# CAN_Module.net
KiCad netlist of a schematic drawn in Altium Designer
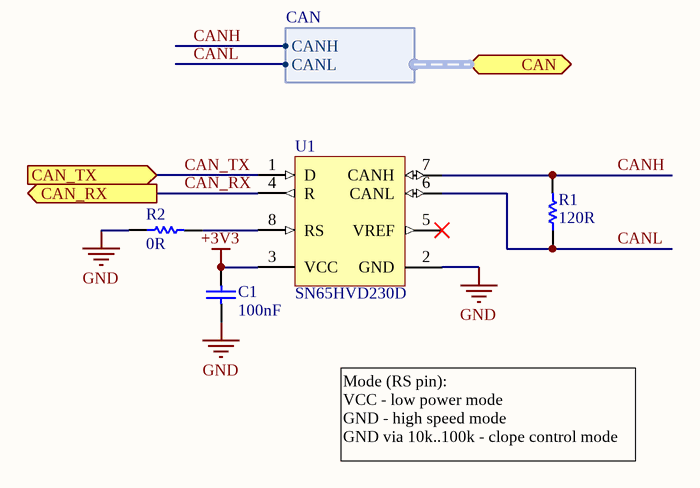
[diagram p0: CAN_Module.SchDoc]

(export (version "E")
  (design (tool "Eeschema 10.0.6"))
  (components
    (comp (ref "C1")
      (value "100nF")
      (footprint "CAP_0805_IPC_MD")
      (description "Capacitor")
      (fields (field (name "MANUFACTURER") "Samsung") (field (name "Comment") "Cap"))
      (libsource (lib "DataLogger") (part "Cap"))
    )
    (comp (ref "R1")
      (value "120R")
      (footprint "RES_1206_IPC_MD")
      (description "Resistor")
      (fields (field (name "Comment") "Res"))
      (libsource (lib "DataLogger") (part "Res"))
    )
    (comp (ref "R2")
      (value "0R")
      (footprint "RES_0805_IPC_MD")
      (description "Resistor")
      (fields (field (name "Comment") "Res"))
      (libsource (lib "DataLogger") (part "Res"))
    )
    (comp (ref "U1")
      (value "SN65HVD230D")
      (footprint "SOIC_8_IPC_MD")
      (fields (field (name "MANUFACTURER") "Texas Instruments") (field (name "PARTNUMBER") "SN65HVD230DR"))
      (libsource (lib "DataLogger") (part "SN65HVD230DR"))
    )
  )
  (nets
    (net (code "2") (name "+3V3") (class "Default")
      (node (ref "C1") (pin "2") (pinfunction "2_2") (pintype "passive"))
      (node (ref "U1") (pin "3") (pinfunction "VCC_3") (pintype "power_in"))
    )
    (net (code "3") (name "/CANH") (class "Default")
      (node (ref "R1") (pin "2") (pinfunction "2_2") (pintype "passive"))
      (node (ref "U1") (pin "7") (pinfunction "CANH_7") (pintype "bidirectional"))
    )
    (net (code "4") (name "/CANL") (class "Default")
      (node (ref "R1") (pin "1") (pinfunction "1_1") (pintype "passive"))
      (node (ref "U1") (pin "6") (pinfunction "CANL_6") (pintype "bidirectional"))
    )
    (net (code "5") (name "/CAN_RX") (class "Default")
      (node (ref "U1") (pin "4") (pinfunction "R_4") (pintype "output"))
    )
    (net (code "6") (name "/CAN_TX") (class "Default")
      (node (ref "U1") (pin "1") (pinfunction "D_1") (pintype "input"))
    )
    (net (code "8") (name "GND") (class "Default")
      (node (ref "C1") (pin "1") (pinfunction "1_1") (pintype "passive"))
      (node (ref "R2") (pin "1") (pinfunction "1_1") (pintype "passive"))
      (node (ref "U1") (pin "2") (pinfunction "GND_2") (pintype "power_in"))
    )
    (net (code "9") (name "Net-(U1-RS)") (class "Default")
      (node (ref "R2") (pin "2") (pinfunction "2_2") (pintype "passive"))
      (node (ref "U1") (pin "8") (pinfunction "RS_8") (pintype "input"))
    )
    (net (code "10") (name "unconnected-(U1-VREF-Pad5)") (class "Default")
      (node (ref "U1") (pin "5") (pinfunction "VREF_5") (pintype "output+no_connect"))
    )
  )
)
